# RemoteControl.net
KiCad netlist of a schematic drawn in Altium Designer
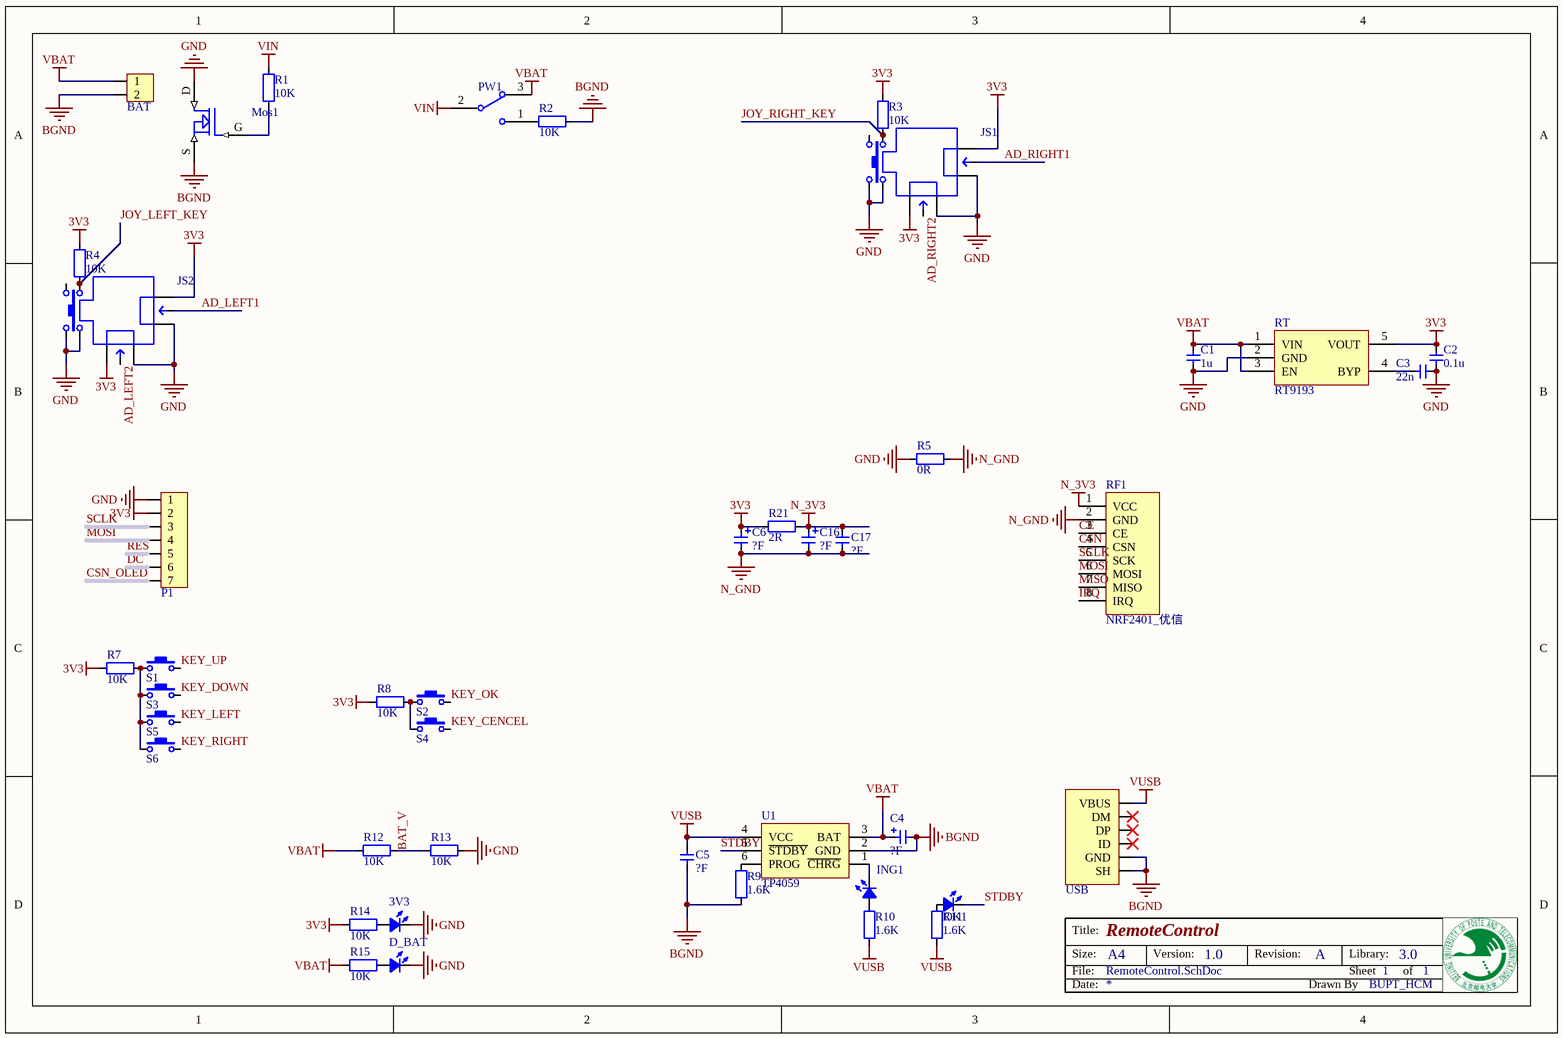
[diagram p0: RemoteControl.SchDoc]

(export (version "E")
  (design (tool "Eeschema 10.0.6"))
  (components
    (comp (ref "3V3")
      (value "LED_0805")
      (footprint "PCB_ActiveLED:LED_0805_RED")
      (description "LED")
      (libsource (lib "SCH_Active") (part "LED_0805"))
    )
    (comp (ref "BAT")
      (value "HDR1x2_2.54")
      (footprint "PCB_ConnectorHDR:HDR1X2_2.54_90")
      (description "Header")
      (libsource (lib "SCH_ConnectorHDR") (part "HDR1x2_2.54"))
    )
    (comp (ref "C1")
      (value "1u")
      (footprint "PCB_PassiveCap:CAP_0603")
      (description "Capacitor")
      (fields (field (name "Comment") "Cap_0603"))
      (libsource (lib "SCH_Passive") (part "Cap_0603"))
    )
    (comp (ref "C2")
      (value "0.1u")
      (footprint "PCB_PassiveCap:CAP_0603")
      (description "Capacitor")
      (fields (field (name "Comment") "Cap_0603"))
      (libsource (lib "SCH_Passive") (part "Cap_0603"))
    )
    (comp (ref "C3")
      (value "22n")
      (footprint "PCB_PassiveCap:CAP_0603")
      (description "Capacitor")
      (fields (field (name "Comment") "Cap_0603"))
      (libsource (lib "SCH_Passive") (part "Cap_0603"))
    )
    (comp (ref "C4")
      (value "?F")
      (footprint "PCB_PassiveCap:CAP_TAN_D2917")
      (description "Capacitor")
      (fields (field (name "Comment") "Cap_Tan_2917"))
      (libsource (lib "SCH_Passive") (part "Cap_Tan_2917"))
    )
    (comp (ref "C5")
      (value "?F")
      (footprint "PCB_PassiveCap:CAP_0805")
      (description "Capacitor")
      (fields (field (name "Comment") "Cap_0805"))
      (libsource (lib "SCH_Passive") (part "Cap_0805"))
    )
    (comp (ref "C6")
      (value "?F")
      (footprint "PCB_PassiveCap:CAP_TAN_A1206")
      (description "Capacitor")
      (fields (field (name "Comment") "Cap_Tan_1206"))
      (libsource (lib "SCH_Passive") (part "Cap_Tan_1206"))
    )
    (comp (ref "C16")
      (value "?F")
      (footprint "PCB_PassiveCap:CAP_TAN_A1206")
      (description "Capacitor")
      (fields (field (name "Comment") "Cap_Tan_1206"))
      (libsource (lib "SCH_Passive") (part "Cap_Tan_1206"))
    )
    (comp (ref "C17")
      (value "?F")
      (footprint "PCB_PassiveCap:CAP_0603")
      (description "Capacitor")
      (fields (field (name "Comment") "Cap_0603"))
      (libsource (lib "SCH_Passive") (part "Cap_0603"))
    )
    (comp (ref "D_BAT")
      (value "LED_0805")
      (footprint "PCB_ActiveLED:LED_0805_RED")
      (description "LED")
      (libsource (lib "SCH_Active") (part "LED_0805"))
    )
    (comp (ref "ING1")
      (value "LED_0805")
      (footprint "PCB_ActiveLED:LED_0805_RED")
      (description "LED")
      (libsource (lib "SCH_Active") (part "LED_0805"))
    )
    (comp (ref "JS1")
      (value "JoyStick")
      (footprint "PCB_Switch:JoyStick")
      (libsource (lib "SCH_Switch") (part "JoyStick"))
    )
    (comp (ref "JS2")
      (value "JoyStick")
      (footprint "PCB_Switch:JoyStick")
      (libsource (lib "SCH_Switch") (part "JoyStick"))
    )
    (comp (ref "Mos1")
      (value "MOSFET N")
      (footprint "Nmos_SOT23")
      (description "MOS SOT23")
      (libsource (lib "SCH_Active") (part "MOSFET N"))
    )
    (comp (ref "OK1")
      (value "LED_0805")
      (footprint "PCB_ActiveLED:LED_0805_GREEN")
      (description "LED")
      (libsource (lib "SCH_Active") (part "LED_0805"))
    )
    (comp (ref "P1")
      (value "HDR1x7_2.54")
      (footprint "PCB_ConnectorHDR:HDR1X7_2.54_180")
      (description "Header")
      (libsource (lib "SCH_ConnectorHDR") (part "HDR1x7_2.54T"))
    )
    (comp (ref "PW1")
      (value "SwitchSPDT_2.8x6.6_90")
      (footprint "PCB_Switch:SwitchSPDT_2.8X6.6_90")
      (description "Switch")
      (libsource (lib "SCH_Switch") (part "SwitchSPDT_2.8x6.6_90"))
    )
    (comp (ref "R1")
      (value "10K")
      (footprint "PCB_PassiveRes:RES_0603")
      (description "Resistor")
      (fields (field (name "Comment") "Res_0603"))
      (libsource (lib "") (part "Res_0603_2"))
    )
    (comp (ref "R2")
      (value "10K")
      (footprint "PCB_PassiveRes:RES_0603")
      (description "Resistor")
      (fields (field (name "Comment") "Res_0603"))
      (libsource (lib "") (part "Res_0603_3"))
    )
    (comp (ref "R3")
      (value "10K")
      (footprint "PCB_PassiveRes:RES_0603")
      (description "Resistor")
      (fields (field (name "Comment") "Res_0603"))
      (libsource (lib "") (part "Res_0603_2"))
    )
    (comp (ref "R4")
      (value "10K")
      (footprint "PCB_PassiveRes:RES_0603")
      (description "Resistor")
      (fields (field (name "Comment") "Res_0603"))
      (libsource (lib "") (part "Res_0603_2"))
    )
    (comp (ref "R5")
      (value "0R")
      (footprint "PCB_PassiveRes:RES_0603")
      (description "Resistor")
      (fields (field (name "Comment") "Res_0603"))
      (libsource (lib "SCH_Passive") (part "Res_0603"))
    )
    (comp (ref "R7")
      (value "10K")
      (footprint "PCB_PassiveRes:RES_0603")
      (description "Resistor")
      (fields (field (name "Comment") "Res_0603"))
      (libsource (lib "SCH_Passive") (part "Res_0603"))
    )
    (comp (ref "R8")
      (value "10K")
      (footprint "PCB_PassiveRes:RES_0603")
      (description "Resistor")
      (fields (field (name "Comment") "Res_0603"))
      (libsource (lib "SCH_Passive") (part "Res_0603"))
    )
    (comp (ref "R9")
      (value "1.6K")
      (footprint "PCB_PassiveRes:RES_0603")
      (description "Resistor")
      (fields (field (name "Comment") "Res_0603"))
      (libsource (lib "") (part "Res_0603_1"))
    )
    (comp (ref "R10")
      (value "1.6K")
      (footprint "PCB_PassiveRes:RES_0603")
      (description "Resistor")
      (fields (field (name "Comment") "Res_0603"))
      (libsource (lib "") (part "Res_0603_1"))
    )
    (comp (ref "R11")
      (value "1.6K")
      (footprint "PCB_PassiveRes:RES_0603")
      (description "Resistor")
      (fields (field (name "Comment") "Res_0603"))
      (libsource (lib "") (part "Res_0603_1"))
    )
    (comp (ref "R12")
      (value "10K")
      (footprint "PCB_PassiveRes:RES_0603")
      (description "Resistor")
      (fields (field (name "Comment") "Res_0603"))
      (libsource (lib "SCH_Passive") (part "Res_0603"))
    )
    (comp (ref "R13")
      (value "10K")
      (footprint "PCB_PassiveRes:RES_0603")
      (description "Resistor")
      (fields (field (name "Comment") "Res_0603"))
      (libsource (lib "SCH_Passive") (part "Res_0603"))
    )
    (comp (ref "R14")
      (value "10K")
      (footprint "PCB_PassiveRes:RES_0603")
      (description "Resistor")
      (fields (field (name "Comment") "Res_0603"))
      (libsource (lib "") (part "Res_0603_3"))
    )
    (comp (ref "R15")
      (value "10K")
      (footprint "PCB_PassiveRes:RES_0603")
      (description "Resistor")
      (fields (field (name "Comment") "Res_0603"))
      (libsource (lib "") (part "Res_0603_3"))
    )
    (comp (ref "R21")
      (value "2R")
      (footprint "PCB_PassiveRes:RES_0603")
      (description "Resistor")
      (fields (field (name "Comment") "Res_0603"))
      (libsource (lib "SCH_Passive") (part "Res_0603"))
    )
    (comp (ref "RF1")
      (value "NRF2401_优信")
      (footprint "nrf24l01_youxin")
      (libsource (lib "SCH_Module") (part "NRF2401_优信"))
    )
    (comp (ref "RT")
      (value "RT9193")
      (footprint "PCB_IntegratedCircuit:SOT23-5")
      (description "Power")
      (libsource (lib "SCH_IntegratedCircuit") (part "RT9193"))
    )
    (comp (ref "S1")
      (value "ButtonTACT_3x6x2.5_180")
      (footprint "PCB_Switch:ButtonTACT_3x6x2.5_180")
      (description "Button")
      (libsource (lib "SCH_Switch") (part "ButtonTACT_3x6x2.5_180"))
    )
    (comp (ref "S2")
      (value "ButtonTACT_3x6x2.5_180")
      (footprint "PCB_Switch:ButtonTACT_3x6x2.5_180")
      (description "Button")
      (libsource (lib "SCH_Switch") (part "ButtonTACT_3x6x2.5_180"))
    )
    (comp (ref "S3")
      (value "ButtonTACT_3x6x2.5_180")
      (footprint "PCB_Switch:ButtonTACT_3x6x2.5_180")
      (description "Button")
      (libsource (lib "SCH_Switch") (part "ButtonTACT_3x6x2.5_180"))
    )
    (comp (ref "S4")
      (value "ButtonTACT_3x6x2.5_180")
      (footprint "PCB_Switch:ButtonTACT_3x6x2.5_180")
      (description "Button")
      (libsource (lib "SCH_Switch") (part "ButtonTACT_3x6x2.5_180"))
    )
    (comp (ref "S5")
      (value "ButtonTACT_3x6x2.5_180")
      (footprint "PCB_Switch:ButtonTACT_3x6x2.5_180")
      (description "Button")
      (libsource (lib "SCH_Switch") (part "ButtonTACT_3x6x2.5_180"))
    )
    (comp (ref "S6")
      (value "ButtonTACT_3x6x2.5_180")
      (footprint "PCB_Switch:ButtonTACT_3x6x2.5_180")
      (description "Button")
      (libsource (lib "SCH_Switch") (part "ButtonTACT_3x6x2.5_180"))
    )
    (comp (ref "U1")
      (value "TP4059")
      (footprint "SOT23-6")
      (libsource (lib "SCH_IntegratedCircuit") (part "TP4059"))
    )
    (comp (ref "USB")
      (value "USB_Micro")
      (footprint "PCB_USB:USB_Micro-AB")
      (description "USB")
      (libsource (lib "SCH_USB") (part "USB_Micro"))
    )
  )
  (nets
    (net (code "1") (name "/AD_LEFT1") (class "Default")
      (node (ref "JS2") (pin "5") (pinfunction "5_5") (pintype "passive"))
    )
    (net (code "2") (name "/AD_LEFT2") (class "Default")
      (node (ref "JS2") (pin "2") (pinfunction "2_2") (pintype "passive"))
    )
    (net (code "3") (name "/AD_RIGHT1") (class "Default")
      (node (ref "JS1") (pin "5") (pinfunction "5_5") (pintype "passive"))
    )
    (net (code "4") (name "/AD_RIGHT2") (class "Default")
      (node (ref "JS1") (pin "2") (pinfunction "2_2") (pintype "passive"))
    )
    (net (code "5") (name "/BAT_V") (class "Default")
      (node (ref "R12") (pin "1") (pinfunction "1_1") (pintype "passive"))
      (node (ref "R13") (pin "2") (pinfunction "2_2") (pintype "passive"))
    )
    (net (code "6") (name "/CE") (class "Default")
      (node (ref "RF1") (pin "3") (pinfunction "CE_3") (pintype "passive"))
    )
    (net (code "7") (name "/CSN") (class "Default")
      (node (ref "RF1") (pin "4") (pinfunction "CSN_4") (pintype "passive"))
    )
    (net (code "8") (name "/CSN_OLED") (class "Default")
      (node (ref "P1") (pin "7") (pinfunction "7_7") (pintype "passive"))
    )
    (net (code "9") (name "/DC") (class "Default")
      (node (ref "P1") (pin "6") (pinfunction "6_6") (pintype "passive"))
    )
    (net (code "10") (name "/IRQ") (class "Default")
      (node (ref "RF1") (pin "8") (pinfunction "IRQ_8") (pintype "passive"))
    )
    (net (code "11") (name "/JOY_LEFT_KEY") (class "Default")
      (node (ref "JS2") (pin "9") (pinfunction "9_9") (pintype "passive"))
      (node (ref "R4") (pin "1") (pinfunction "1_1") (pintype "passive"))
    )
    (net (code "12") (name "/JOY_RIGHT_KEY") (class "Default")
      (node (ref "JS1") (pin "9") (pinfunction "9_9") (pintype "passive"))
      (node (ref "R3") (pin "1") (pinfunction "1_1") (pintype "passive"))
    )
    (net (code "13") (name "/KEY_CENCEL") (class "Default")
      (node (ref "S4") (pin "2") (pinfunction "2_2") (pintype "passive"))
    )
    (net (code "14") (name "/KEY_DOWN") (class "Default")
      (node (ref "S3") (pin "2") (pinfunction "2_2") (pintype "passive"))
    )
    (net (code "15") (name "/KEY_LEFT") (class "Default")
      (node (ref "S5") (pin "2") (pinfunction "2_2") (pintype "passive"))
    )
    (net (code "16") (name "/KEY_OK") (class "Default")
      (node (ref "S2") (pin "2") (pinfunction "2_2") (pintype "passive"))
    )
    (net (code "17") (name "/KEY_RIGHT") (class "Default")
      (node (ref "S6") (pin "2") (pinfunction "2_2") (pintype "passive"))
    )
    (net (code "18") (name "/KEY_UP") (class "Default")
      (node (ref "S1") (pin "2") (pinfunction "2_2") (pintype "passive"))
    )
    (net (code "19") (name "/MISO") (class "Default")
      (node (ref "RF1") (pin "7") (pinfunction "MISO_7") (pintype "passive"))
    )
    (net (code "20") (name "/MOSI") (class "Default")
      (node (ref "P1") (pin "4") (pinfunction "4_4") (pintype "passive"))
      (node (ref "RF1") (pin "6") (pinfunction "MOSI_6") (pintype "passive"))
    )
    (net (code "21") (name "/RES") (class "Default")
      (node (ref "P1") (pin "5") (pinfunction "5_5") (pintype "passive"))
    )
    (net (code "22") (name "/SCLK") (class "Default")
      (node (ref "P1") (pin "3") (pinfunction "3_3") (pintype "passive"))
      (node (ref "RF1") (pin "5") (pinfunction "SCK_5") (pintype "passive"))
    )
    (net (code "23") (name "/STDBY") (class "Default")
      (node (ref "OK1") (pin "2") (pinfunction "K_2") (pintype "passive"))
      (node (ref "U1") (pin "5") (pinfunction "~{STDBY}_5") (pintype "passive"))
    )
    (net (code "24") (name "3V3") (class "Default")
      (node (ref "C2") (pin "2") (pinfunction "2_2") (pintype "passive"))
      (node (ref "C6") (pin "1") (pinfunction "1_1") (pintype "passive"))
      (node (ref "JS1") (pin "1") (pinfunction "1_1") (pintype "passive"))
      (node (ref "JS1") (pin "6") (pinfunction "6_6") (pintype "passive"))
      (node (ref "JS2") (pin "1") (pinfunction "1_1") (pintype "passive"))
      (node (ref "JS2") (pin "6") (pinfunction "6_6") (pintype "passive"))
      (node (ref "P1") (pin "2") (pinfunction "2_2") (pintype "passive"))
      (node (ref "R14") (pin "1") (pinfunction "1_1") (pintype "passive"))
      (node (ref "R21") (pin "2") (pinfunction "2_2") (pintype "passive"))
      (node (ref "R3") (pin "2") (pinfunction "2_2") (pintype "passive"))
      (node (ref "R4") (pin "2") (pinfunction "2_2") (pintype "passive"))
      (node (ref "R7") (pin "2") (pinfunction "2_2") (pintype "passive"))
      (node (ref "R8") (pin "2") (pinfunction "2_2") (pintype "passive"))
      (node (ref "RT") (pin "5") (pinfunction "VOUT_5") (pintype "passive"))
    )
    (net (code "25") (name "BGND") (class "Default")
      (node (ref "BAT") (pin "2") (pinfunction "2_2") (pintype "passive"))
      (node (ref "C4") (pin "2") (pinfunction "2_2") (pintype "passive"))
      (node (ref "C5") (pin "1") (pinfunction "1_1") (pintype "passive"))
      (node (ref "Mos1") (pin "S") (pinfunction "S_S") (pintype "input"))
      (node (ref "R2") (pin "2") (pinfunction "2_2") (pintype "passive"))
      (node (ref "R9") (pin "2") (pinfunction "2_2") (pintype "passive"))
      (node (ref "U1") (pin "2") (pinfunction "GND_2") (pintype "passive"))
      (node (ref "USB") (pin "0") (pinfunction "SH_0") (pintype "passive"))
      (node (ref "USB") (pin "5") (pinfunction "GND_5") (pintype "passive"))
    )
    (net (code "26") (name "GND") (class "Default")
      (node (ref "3V3") (pin "2") (pinfunction "K_2") (pintype "passive"))
      (node (ref "C1") (pin "1") (pinfunction "1_1") (pintype "passive"))
      (node (ref "C2") (pin "1") (pinfunction "1_1") (pintype "passive"))
      (node (ref "C3") (pin "1") (pinfunction "1_1") (pintype "passive"))
      (node (ref "D_BAT") (pin "2") (pinfunction "K_2") (pintype "passive"))
      (node (ref "JS1") (pin "10") (pinfunction "10_10") (pintype "passive"))
      (node (ref "JS1") (pin "3") (pinfunction "3_3") (pintype "passive"))
      (node (ref "JS1") (pin "4") (pinfunction "4_4") (pintype "passive"))
      (node (ref "JS1") (pin "8") (pinfunction "8_8") (pintype "passive"))
      (node (ref "JS2") (pin "10") (pinfunction "10_10") (pintype "passive"))
      (node (ref "JS2") (pin "3") (pinfunction "3_3") (pintype "passive"))
      (node (ref "JS2") (pin "4") (pinfunction "4_4") (pintype "passive"))
      (node (ref "JS2") (pin "8") (pinfunction "8_8") (pintype "passive"))
      (node (ref "Mos1") (pin "D") (pinfunction "D_D") (pintype "input"))
      (node (ref "P1") (pin "1") (pinfunction "1_1") (pintype "passive"))
      (node (ref "R13") (pin "1") (pinfunction "1_1") (pintype "passive"))
      (node (ref "R5") (pin "2") (pinfunction "2_2") (pintype "passive"))
      (node (ref "RT") (pin "2") (pinfunction "GND_2") (pintype "passive"))
    )
    (net (code "27") (name "N_3V3") (class "Default")
      (node (ref "C16") (pin "1") (pinfunction "1_1") (pintype "passive"))
      (node (ref "C17") (pin "2") (pinfunction "2_2") (pintype "passive"))
      (node (ref "R21") (pin "1") (pinfunction "1_1") (pintype "passive"))
      (node (ref "RF1") (pin "1") (pinfunction "VCC_1") (pintype "passive"))
    )
    (net (code "28") (name "N_GND") (class "Default")
      (node (ref "C16") (pin "2") (pinfunction "2_2") (pintype "passive"))
      (node (ref "C17") (pin "1") (pinfunction "1_1") (pintype "passive"))
      (node (ref "C6") (pin "2") (pinfunction "2_2") (pintype "passive"))
      (node (ref "R5") (pin "1") (pinfunction "1_1") (pintype "passive"))
      (node (ref "RF1") (pin "2") (pinfunction "GND_2") (pintype "passive"))
    )
    (net (code "29") (name "Net-(3V3-A)") (class "Default")
      (node (ref "3V3") (pin "1") (pinfunction "A_1") (pintype "passive"))
      (node (ref "R14") (pin "2") (pinfunction "2_2") (pintype "passive"))
    )
    (net (code "30") (name "Net-(D_BAT-A)") (class "Default")
      (node (ref "D_BAT") (pin "1") (pinfunction "A_1") (pintype "passive"))
      (node (ref "R15") (pin "2") (pinfunction "2_2") (pintype "passive"))
    )
    (net (code "31") (name "Net-(ING1-A)") (class "Default")
      (node (ref "ING1") (pin "1") (pinfunction "A_1") (pintype "passive"))
      (node (ref "R10") (pin "1") (pinfunction "1_1") (pintype "passive"))
    )
    (net (code "32") (name "Net-(ING1-K)") (class "Default")
      (node (ref "ING1") (pin "2") (pinfunction "K_2") (pintype "passive"))
      (node (ref "U1") (pin "1") (pinfunction "~{CHRG}_1") (pintype "passive"))
    )
    (net (code "33") (name "Net-(Mos1-PadG)") (class "Default")
      (node (ref "Mos1") (pin "G") (pinfunction "G_G") (pintype "input"))
      (node (ref "R1") (pin "1") (pinfunction "1_1") (pintype "passive"))
    )
    (net (code "34") (name "Net-(OK1-A)") (class "Default")
      (node (ref "OK1") (pin "1") (pinfunction "A_1") (pintype "passive"))
      (node (ref "R11") (pin "1") (pinfunction "1_1") (pintype "passive"))
    )
    (net (code "35") (name "Net-(PW1-Pad1)") (class "Default")
      (node (ref "PW1") (pin "1") (pinfunction "1_1") (pintype "passive"))
      (node (ref "R2") (pin "1") (pinfunction "1_1") (pintype "passive"))
    )
    (net (code "36") (name "Net-(R7-Pad1)") (class "Default")
      (node (ref "R7") (pin "1") (pinfunction "1_1") (pintype "passive"))
      (node (ref "S1") (pin "1") (pinfunction "1_1") (pintype "passive"))
      (node (ref "S3") (pin "1") (pinfunction "1_1") (pintype "passive"))
      (node (ref "S5") (pin "1") (pinfunction "1_1") (pintype "passive"))
      (node (ref "S6") (pin "1") (pinfunction "1_1") (pintype "passive"))
    )
    (net (code "37") (name "Net-(R8-Pad1)") (class "Default")
      (node (ref "R8") (pin "1") (pinfunction "1_1") (pintype "passive"))
      (node (ref "S2") (pin "1") (pinfunction "1_1") (pintype "passive"))
      (node (ref "S4") (pin "1") (pinfunction "1_1") (pintype "passive"))
    )
    (net (code "38") (name "Net-(RT-BYP)") (class "Default")
      (node (ref "C3") (pin "2") (pinfunction "2_2") (pintype "passive"))
      (node (ref "RT") (pin "4") (pinfunction "BYP_4") (pintype "passive"))
    )
    (net (code "39") (name "Net-(U1-PROG)") (class "Default")
      (node (ref "R9") (pin "1") (pinfunction "1_1") (pintype "passive"))
      (node (ref "U1") (pin "6") (pinfunction "PROG_6") (pintype "passive"))
    )
    (net (code "40") (name "VBAT") (class "Default")
      (node (ref "BAT") (pin "1") (pinfunction "1_1") (pintype "passive"))
      (node (ref "C1") (pin "2") (pinfunction "2_2") (pintype "passive"))
      (node (ref "C4") (pin "1") (pinfunction "1_1") (pintype "passive"))
      (node (ref "PW1") (pin "3") (pinfunction "3_3") (pintype "passive"))
      (node (ref "R12") (pin "2") (pinfunction "2_2") (pintype "passive"))
      (node (ref "R15") (pin "1") (pinfunction "1_1") (pintype "passive"))
      (node (ref "RT") (pin "1") (pinfunction "VIN_1") (pintype "passive"))
      (node (ref "RT") (pin "3") (pinfunction "EN_3") (pintype "power_in"))
      (node (ref "U1") (pin "3") (pinfunction "BAT_3") (pintype "passive"))
    )
    (net (code "41") (name "VIN") (class "Default")
      (node (ref "PW1") (pin "2") (pinfunction "2_2") (pintype "passive"))
      (node (ref "R1") (pin "2") (pinfunction "2_2") (pintype "passive"))
    )
    (net (code "42") (name "VUSB") (class "Default")
      (node (ref "C5") (pin "2") (pinfunction "2_2") (pintype "passive"))
      (node (ref "R10") (pin "2") (pinfunction "2_2") (pintype "passive"))
      (node (ref "R11") (pin "2") (pinfunction "2_2") (pintype "passive"))
      (node (ref "U1") (pin "4") (pinfunction "VCC_4") (pintype "passive"))
      (node (ref "USB") (pin "1") (pinfunction "VBUS_1") (pintype "passive"))
    )
    (net (code "43") (name "unconnected-(JS1-Pad7)") (class "Default")
      (node (ref "JS1") (pin "7") (pinfunction "7_7") (pintype "passive"))
    )
    (net (code "44") (name "unconnected-(JS2-Pad7)") (class "Default")
      (node (ref "JS2") (pin "7") (pinfunction "7_7") (pintype "passive"))
    )
    (net (code "45") (name "unconnected-(USB-DM-Pad2)") (class "Default")
      (node (ref "USB") (pin "2") (pinfunction "DM_2") (pintype "passive+no_connect"))
    )
    (net (code "46") (name "unconnected-(USB-DP-Pad3)") (class "Default")
      (node (ref "USB") (pin "3") (pinfunction "DP_3") (pintype "passive+no_connect"))
    )
    (net (code "47") (name "unconnected-(USB-ID-Pad4)") (class "Default")
      (node (ref "USB") (pin "4") (pinfunction "ID_4") (pintype "passive+no_connect"))
    )
  )
)
